# FeatherAB1805-Li.net
KiCad netlist of a schematic drawn in EAGLE
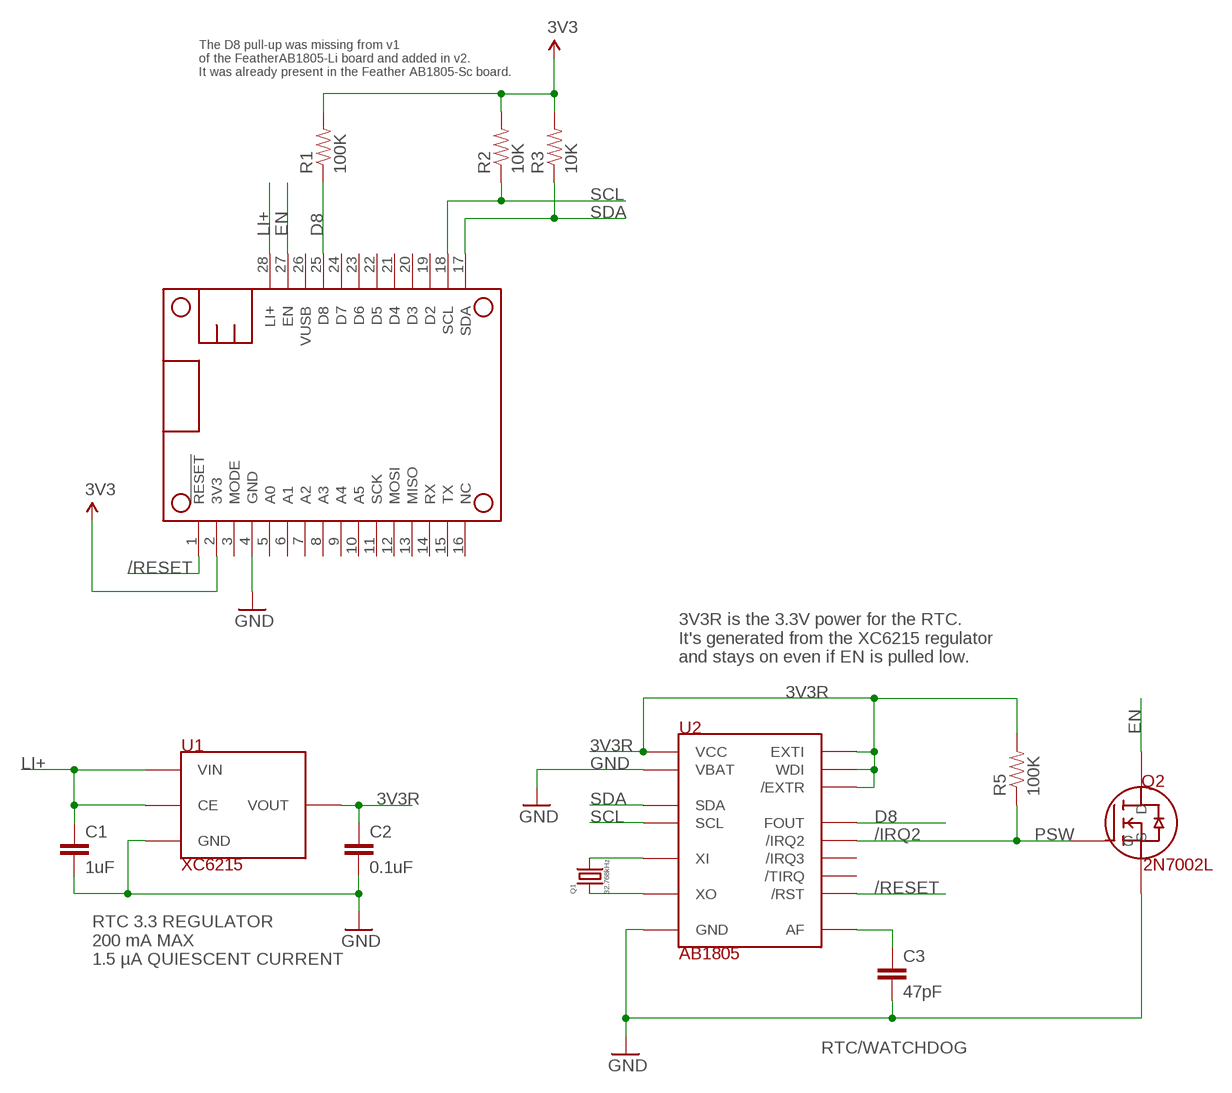
[diagram p0: schematic, sheet 1]

(export (version "E")
  (design (tool "Eeschema 10.0.6"))
  (components
    (comp (ref "C1")
      (value "1uF")
      (footprint "eagle-import:0603-CAP")
      (libsource (lib "eagle-import") (part "CAP-1UF-0603.DEV"))
    )
    (comp (ref "C2")
      (value "0.1uF")
      (footprint "eagle-import:0603-CAP")
      (libsource (lib "eagle-import") (part "CAP-0.1UF-0603"))
    )
    (comp (ref "C3")
      (value "47pF")
      (footprint "eagle-import:0603-CAP")
      (libsource (lib "eagle-import") (part "CAP-47PF-0603"))
    )
    (comp (ref "MS1")
      (value "FEATHERWING_NODIM")
      (footprint "eagle-import:FEATHERWING_NODIM")
      (libsource (lib "eagle-import") (part "FEATHERWING_NODIM"))
    )
    (comp (ref "Q1")
      (value "32.768kHz")
      (footprint "eagle-import:ABS07-120-CRYSTAL")
      (libsource (lib "eagle-import") (part "ABS07-120-32.768KHZ"))
    )
    (comp (ref "Q2")
      (value "2N7002L")
      (footprint "eagle-import:2N7002L")
      (libsource (lib "eagle-import") (part "2N7002L"))
    )
    (comp (ref "R1")
      (value "100K")
      (footprint "eagle-import:0603-RES")
      (libsource (lib "eagle-import") (part "RES-100K-0603"))
    )
    (comp (ref "R2")
      (value "10K")
      (footprint "eagle-import:0603-RES")
      (libsource (lib "eagle-import") (part "RES-10K-06030603"))
    )
    (comp (ref "R3")
      (value "10K")
      (footprint "eagle-import:0603-RES")
      (libsource (lib "eagle-import") (part "RES-10K-06030603"))
    )
    (comp (ref "R5")
      (value "100K")
      (footprint "eagle-import:0603-RES")
      (libsource (lib "eagle-import") (part "RES-100K-0603"))
    )
    (comp (ref "U1")
      (value "XC6215")
      (footprint "eagle-import:SOT-25-TOREX")
      (libsource (lib "eagle-import") (part "XC6215"))
    )
    (comp (ref "U2")
      (value "AB1805")
      (footprint "eagle-import:16-VFQFN-ABRACON")
      (libsource (lib "eagle-import") (part "AB1805"))
    )
  )
  (nets
    (net (code "1") (name "/3V3R") (class "Default")
      (node (ref "C2") (pin "1") (pinfunction "1_1") (pintype "passive"))
      (node (ref "R5") (pin "2") (pinfunction "2_2") (pintype "passive"))
      (node (ref "U1") (pin "5") (pinfunction "VOUT_5") (pintype "passive"))
      (node (ref "U2") (pin "10") (pinfunction "EXTI_10") (pintype "input"))
      (node (ref "U2") (pin "13") (pinfunction "VCC_13") (pintype "passive"))
      (node (ref "U2") (pin "2") (pinfunction "WDI_2") (pintype "input"))
      (node (ref "U2") (pin "3") (pinfunction "/EXTR_3") (pintype "input"))
    )
    (net (code "2") (name "/D8") (class "Default")
      (node (ref "MS1") (pin "25") (pinfunction "D8_25") (pintype "bidirectional"))
      (node (ref "R1") (pin "1") (pinfunction "1_1") (pintype "passive"))
      (node (ref "U2") (pin "11") (pinfunction "FOUT_11") (pintype "output"))
    )
    (net (code "3") (name "/EN") (class "Default")
      (node (ref "MS1") (pin "27") (pinfunction "EN_27") (pintype "passive"))
      (node (ref "Q2") (pin "3") (pinfunction "D_3") (pintype "bidirectional"))
    )
    (net (code "4") (name "/LI+") (class "Default")
      (node (ref "C1") (pin "1") (pinfunction "1_1") (pintype "passive"))
      (node (ref "MS1") (pin "28") (pinfunction "LI+_28") (pintype "power_in"))
      (node (ref "U1") (pin "1") (pinfunction "VIN_1") (pintype "passive"))
      (node (ref "U1") (pin "3") (pinfunction "CE_3") (pintype "input"))
    )
    (net (code "5") (name "/SCL") (class "Default")
      (node (ref "MS1") (pin "18") (pinfunction "SCL_18") (pintype "bidirectional"))
      (node (ref "R2") (pin "1") (pinfunction "1_1") (pintype "passive"))
      (node (ref "U2") (pin "7") (pinfunction "SCL_7") (pintype "bidirectional"))
    )
    (net (code "6") (name "/SDA") (class "Default")
      (node (ref "MS1") (pin "17") (pinfunction "SDA_17") (pintype "bidirectional"))
      (node (ref "R3") (pin "1") (pinfunction "1_1") (pintype "passive"))
      (node (ref "U2") (pin "6") (pinfunction "SDA_6") (pintype "bidirectional"))
    )
    (net (code "7") (name "/VUSB") (class "Default")
      (node (ref "MS1") (pin "26") (pinfunction "VUSB_26") (pintype "power_in"))
    )
    (net (code "8") (name "/{slash}IRQ2") (class "Default")
      (node (ref "Q2") (pin "1") (pinfunction "G_1") (pintype "bidirectional"))
      (node (ref "R5") (pin "1") (pinfunction "1_1") (pintype "passive"))
      (node (ref "U2") (pin "4") (pinfunction "/IRQ2_4") (pintype "output"))
    )
    (net (code "9") (name "/{slash}RESET") (class "Default")
      (node (ref "MS1") (pin "1") (pinfunction "~{RESET}_1") (pintype "input"))
      (node (ref "U2") (pin "1") (pinfunction "/RST_1") (pintype "output"))
    )
    (net (code "10") (name "3V3") (class "Default")
      (node (ref "MS1") (pin "2") (pinfunction "3V3_2") (pintype "power_in"))
      (node (ref "R1") (pin "2") (pinfunction "2_2") (pintype "passive"))
      (node (ref "R2") (pin "2") (pinfunction "2_2") (pintype "passive"))
      (node (ref "R3") (pin "2") (pinfunction "2_2") (pintype "passive"))
    )
    (net (code "11") (name "GND") (class "Default")
      (node (ref "C1") (pin "2") (pinfunction "2_2") (pintype "passive"))
      (node (ref "C2") (pin "2") (pinfunction "2_2") (pintype "passive"))
      (node (ref "C3") (pin "2") (pinfunction "2_2") (pintype "passive"))
      (node (ref "MS1") (pin "4") (pinfunction "GND_4") (pintype "power_in"))
      (node (ref "Q2") (pin "2") (pinfunction "S_2") (pintype "bidirectional"))
      (node (ref "U1") (pin "2") (pinfunction "GND_2") (pintype "passive"))
      (node (ref "U2") (pin "5") (pinfunction "VBAT_5") (pintype "passive"))
      (node (ref "U2") (pin "9") (pinfunction "GND_9") (pintype "passive"))
      (node (ref "U2") (pin "EP") (pinfunction "GND_EP") (pintype "passive"))
    )
    (net (code "12") (name "Net-(U2-AF)") (class "Default")
      (node (ref "C3") (pin "1") (pinfunction "1_1") (pintype "passive"))
      (node (ref "U2") (pin "14") (pinfunction "AF_14") (pintype "output"))
    )
    (net (code "13") (name "Net-(U2-XI)") (class "Default")
      (node (ref "Q1") (pin "2") (pinfunction "2_2") (pintype "passive"))
      (node (ref "U2") (pin "16") (pinfunction "XI_16") (pintype "bidirectional"))
    )
    (net (code "14") (name "Net-(U2-XO)") (class "Default")
      (node (ref "Q1") (pin "1") (pinfunction "1_1") (pintype "passive"))
      (node (ref "U2") (pin "15") (pinfunction "XO_15") (pintype "bidirectional"))
    )
    (net (code "15") (name "unconnected-(MS1-A0-Pad5)") (class "Default")
      (node (ref "MS1") (pin "5") (pinfunction "A0_5") (pintype "bidirectional"))
    )
    (net (code "16") (name "unconnected-(MS1-A1-Pad6)") (class "Default")
      (node (ref "MS1") (pin "6") (pinfunction "A1_6") (pintype "bidirectional"))
    )
    (net (code "17") (name "unconnected-(MS1-A2-Pad7)") (class "Default")
      (node (ref "MS1") (pin "7") (pinfunction "A2_7") (pintype "bidirectional"))
    )
    (net (code "18") (name "unconnected-(MS1-A3-Pad8)") (class "Default")
      (node (ref "MS1") (pin "8") (pinfunction "A3_8") (pintype "bidirectional"))
    )
    (net (code "19") (name "unconnected-(MS1-A4-Pad9)") (class "Default")
      (node (ref "MS1") (pin "9") (pinfunction "A4_9") (pintype "bidirectional"))
    )
    (net (code "20") (name "unconnected-(MS1-A5-Pad10)") (class "Default")
      (node (ref "MS1") (pin "10") (pinfunction "A5_10") (pintype "bidirectional"))
    )
    (net (code "21") (name "unconnected-(MS1-D2-Pad19)") (class "Default")
      (node (ref "MS1") (pin "19") (pinfunction "D2_19") (pintype "bidirectional"))
    )
    (net (code "22") (name "unconnected-(MS1-D3-Pad20)") (class "Default")
      (node (ref "MS1") (pin "20") (pinfunction "D3_20") (pintype "bidirectional"))
    )
    (net (code "23") (name "unconnected-(MS1-D4-Pad21)") (class "Default")
      (node (ref "MS1") (pin "21") (pinfunction "D4_21") (pintype "bidirectional"))
    )
    (net (code "24") (name "unconnected-(MS1-D5-Pad22)") (class "Default")
      (node (ref "MS1") (pin "22") (pinfunction "D5_22") (pintype "bidirectional"))
    )
    (net (code "25") (name "unconnected-(MS1-D6-Pad23)") (class "Default")
      (node (ref "MS1") (pin "23") (pinfunction "D6_23") (pintype "bidirectional"))
    )
    (net (code "26") (name "unconnected-(MS1-D7-Pad24)") (class "Default")
      (node (ref "MS1") (pin "24") (pinfunction "D7_24") (pintype "bidirectional"))
    )
    (net (code "27") (name "unconnected-(MS1-MISO-Pad13)") (class "Default")
      (node (ref "MS1") (pin "13") (pinfunction "MISO_13") (pintype "bidirectional"))
    )
    (net (code "28") (name "unconnected-(MS1-MODE-Pad3)") (class "Default")
      (node (ref "MS1") (pin "3") (pinfunction "MODE_3") (pintype "passive"))
    )
    (net (code "29") (name "unconnected-(MS1-MOSI-Pad12)") (class "Default")
      (node (ref "MS1") (pin "12") (pinfunction "MOSI_12") (pintype "bidirectional"))
    )
    (net (code "30") (name "unconnected-(MS1-NC-Pad16)") (class "Default")
      (node (ref "MS1") (pin "16") (pinfunction "NC_16") (pintype "passive"))
    )
    (net (code "31") (name "unconnected-(MS1-RX-Pad14)") (class "Default")
      (node (ref "MS1") (pin "14") (pinfunction "RX_14") (pintype "bidirectional"))
    )
    (net (code "32") (name "unconnected-(MS1-SCK-Pad11)") (class "Default")
      (node (ref "MS1") (pin "11") (pinfunction "SCK_11") (pintype "bidirectional"))
    )
    (net (code "33") (name "unconnected-(MS1-TX-Pad15)") (class "Default")
      (node (ref "MS1") (pin "15") (pinfunction "TX_15") (pintype "bidirectional"))
    )
    (net (code "34") (name "unconnected-(U2-{slash}IRQ3-Pad8)") (class "Default")
      (node (ref "U2") (pin "8") (pinfunction "/IRQ3_8") (pintype "output"))
    )
    (net (code "35") (name "unconnected-(U2-{slash}TIRQ-Pad12)") (class "Default")
      (node (ref "U2") (pin "12") (pinfunction "/TIRQ_12") (pintype "output"))
    )
  )
)
